# high_power_amplifier_module.net
KiCad netlist of a schematic drawn in Altium Designer
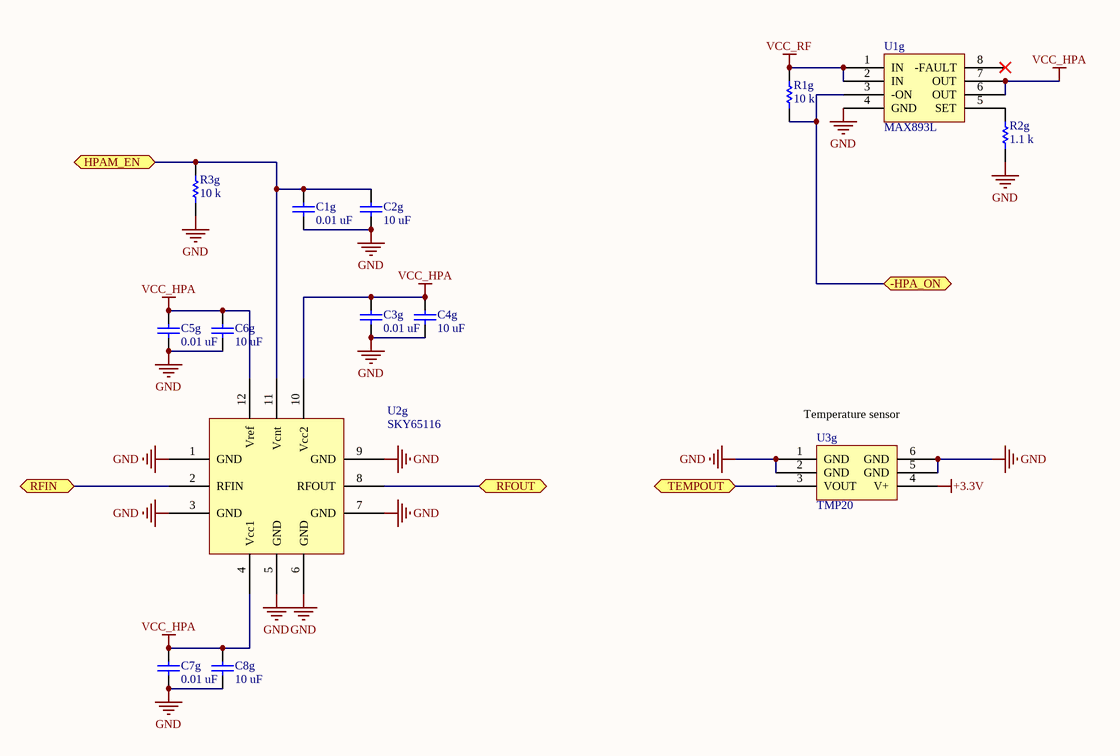
[diagram p0: high power amplifier module.SchDoc]

(export (version "E")
  (design (tool "Eeschema 10.0.6"))
  (components
    (comp (ref "C1g")
      (value "0.01 uF")
      (footprint "0603")
      (description "Capacitor")
      (libsource (lib "allspace_schem") (part "Capacitor"))
    )
    (comp (ref "C2g")
      (value "10 uF")
      (footprint "1206")
      (description "Capacitor")
      (libsource (lib "allspace_schem") (part "Capacitor"))
    )
    (comp (ref "C3g")
      (value "0.01 uF")
      (footprint "0603")
      (description "Capacitor")
      (libsource (lib "allspace_schem") (part "Capacitor"))
    )
    (comp (ref "C4g")
      (value "10 uF")
      (footprint "1206")
      (description "Capacitor")
      (libsource (lib "allspace_schem") (part "Capacitor"))
    )
    (comp (ref "C5g")
      (value "0.01 uF")
      (footprint "0603")
      (description "Capacitor")
      (libsource (lib "allspace_schem") (part "Capacitor"))
    )
    (comp (ref "C6g")
      (value "10 uF")
      (footprint "1206")
      (description "Capacitor")
      (libsource (lib "allspace_schem") (part "Capacitor"))
    )
    (comp (ref "C7g")
      (value "0.01 uF")
      (footprint "0603")
      (description "Capacitor")
      (libsource (lib "allspace_schem") (part "Capacitor"))
    )
    (comp (ref "C8g")
      (value "10 uF")
      (footprint "1206")
      (description "Capacitor")
      (libsource (lib "allspace_schem") (part "Capacitor"))
    )
    (comp (ref "R1g")
      (value "10 k")
      (footprint "0603")
      (description "Resistor")
      (libsource (lib "allspace_schem") (part "Resistor"))
    )
    (comp (ref "R2g")
      (value "1.1 k")
      (footprint "0603")
      (description "Resistor")
      (libsource (lib "allspace_schem") (part "Resistor"))
    )
    (comp (ref "R3g")
      (value "10 k")
      (footprint "0603")
      (description "Resistor")
      (libsource (lib "allspace_schem") (part "Resistor"))
    )
    (comp (ref "U1g")
      (value "MAX893L")
      (footprint "SO-8")
      (libsource (lib "allspace_schem") (part "MAX893L"))
    )
    (comp (ref "U2g")
      (value "SKY65116")
      (footprint "MCM-12")
      (description "Linear RF Power Amplifier")
      (libsource (lib "allspace_schem") (part "SKY65116"))
    )
    (comp (ref "U3g")
      (value "TMP20")
      (footprint "SOT563-6")
      (libsource (lib "allspace_schem") (part "TMP20"))
    )
  )
  (nets
    (net (code "1") (name "+3.3V") (class "Default")
      (node (ref "U3g") (pin "4") (pinfunction "V+_4") (pintype "passive"))
    )
    (net (code "2") (name "/-HPA_ON") (class "Default")
      (node (ref "R1g") (pin "2") (pinfunction "2_2") (pintype "passive"))
      (node (ref "U1g") (pin "3") (pinfunction "-ON_3") (pintype "passive"))
    )
    (net (code "3") (name "/HPAM_EN") (class "Default")
      (node (ref "C1g") (pin "2") (pinfunction "2_2") (pintype "passive"))
      (node (ref "C2g") (pin "2") (pinfunction "2_2") (pintype "passive"))
      (node (ref "R3g") (pin "2") (pinfunction "2_2") (pintype "passive"))
      (node (ref "U2g") (pin "11") (pinfunction "Vcnt_11") (pintype "passive"))
    )
    (net (code "4") (name "/RFIN") (class "Default")
      (node (ref "U2g") (pin "2") (pinfunction "RFIN_2") (pintype "passive"))
    )
    (net (code "5") (name "/RFOUT") (class "Default")
      (node (ref "U2g") (pin "8") (pinfunction "RFOUT_8") (pintype "passive"))
    )
    (net (code "6") (name "/TEMPOUT") (class "Default")
      (node (ref "U3g") (pin "3") (pinfunction "VOUT_3") (pintype "passive"))
    )
    (net (code "7") (name "GND") (class "Default")
      (node (ref "C1g") (pin "1") (pinfunction "1_1") (pintype "passive"))
      (node (ref "C2g") (pin "1") (pinfunction "1_1") (pintype "passive"))
      (node (ref "C3g") (pin "1") (pinfunction "1_1") (pintype "passive"))
      (node (ref "C4g") (pin "1") (pinfunction "1_1") (pintype "passive"))
      (node (ref "C5g") (pin "1") (pinfunction "1_1") (pintype "passive"))
      (node (ref "C6g") (pin "1") (pinfunction "1_1") (pintype "passive"))
      (node (ref "C7g") (pin "1") (pinfunction "1_1") (pintype "passive"))
      (node (ref "C8g") (pin "1") (pinfunction "1_1") (pintype "passive"))
      (node (ref "R2g") (pin "2") (pinfunction "2_2") (pintype "passive"))
      (node (ref "R3g") (pin "1") (pinfunction "1_1") (pintype "passive"))
      (node (ref "U1g") (pin "4") (pinfunction "GND_4") (pintype "passive"))
      (node (ref "U2g") (pin "1") (pinfunction "GND_1") (pintype "passive"))
      (node (ref "U2g") (pin "3") (pinfunction "GND_3") (pintype "passive"))
      (node (ref "U2g") (pin "5") (pinfunction "GND_5") (pintype "passive"))
      (node (ref "U2g") (pin "6") (pinfunction "GND_6") (pintype "passive"))
      (node (ref "U2g") (pin "7") (pinfunction "GND_7") (pintype "passive"))
      (node (ref "U2g") (pin "9") (pinfunction "GND_9") (pintype "passive"))
      (node (ref "U3g") (pin "1") (pinfunction "GND_1") (pintype "passive"))
      (node (ref "U3g") (pin "2") (pinfunction "GND_2") (pintype "passive"))
      (node (ref "U3g") (pin "5") (pinfunction "GND_5") (pintype "passive"))
      (node (ref "U3g") (pin "6") (pinfunction "GND_6") (pintype "passive"))
    )
    (net (code "8") (name "Net-(U1g-SET)") (class "Default")
      (node (ref "R2g") (pin "1") (pinfunction "1_1") (pintype "passive"))
      (node (ref "U1g") (pin "5") (pinfunction "SET_5") (pintype "passive"))
    )
    (net (code "9") (name "VCC_HPA") (class "Default")
      (node (ref "C3g") (pin "2") (pinfunction "2_2") (pintype "passive"))
      (node (ref "C4g") (pin "2") (pinfunction "2_2") (pintype "passive"))
      (node (ref "C5g") (pin "2") (pinfunction "2_2") (pintype "passive"))
      (node (ref "C6g") (pin "2") (pinfunction "2_2") (pintype "passive"))
      (node (ref "C7g") (pin "2") (pinfunction "2_2") (pintype "passive"))
      (node (ref "C8g") (pin "2") (pinfunction "2_2") (pintype "passive"))
      (node (ref "U1g") (pin "6") (pinfunction "OUT_6") (pintype "passive"))
      (node (ref "U1g") (pin "7") (pinfunction "OUT_7") (pintype "passive"))
      (node (ref "U2g") (pin "10") (pinfunction "Vcc2_10") (pintype "passive"))
      (node (ref "U2g") (pin "12") (pinfunction "Vref_12") (pintype "passive"))
      (node (ref "U2g") (pin "4") (pinfunction "Vcc1_4") (pintype "passive"))
    )
    (net (code "10") (name "VCC_RF") (class "Default")
      (node (ref "R1g") (pin "1") (pinfunction "1_1") (pintype "passive"))
      (node (ref "U1g") (pin "1") (pinfunction "IN_1") (pintype "passive"))
      (node (ref "U1g") (pin "2") (pinfunction "IN_2") (pintype "passive"))
    )
    (net (code "11") (name "unconnected-(U1g--FAULT-Pad8)") (class "Default")
      (node (ref "U1g") (pin "8") (pinfunction "-FAULT_8") (pintype "passive+no_connect"))
    )
  )
)
